# Esquematico.net
KiCad netlist of a schematic drawn in EAGLE
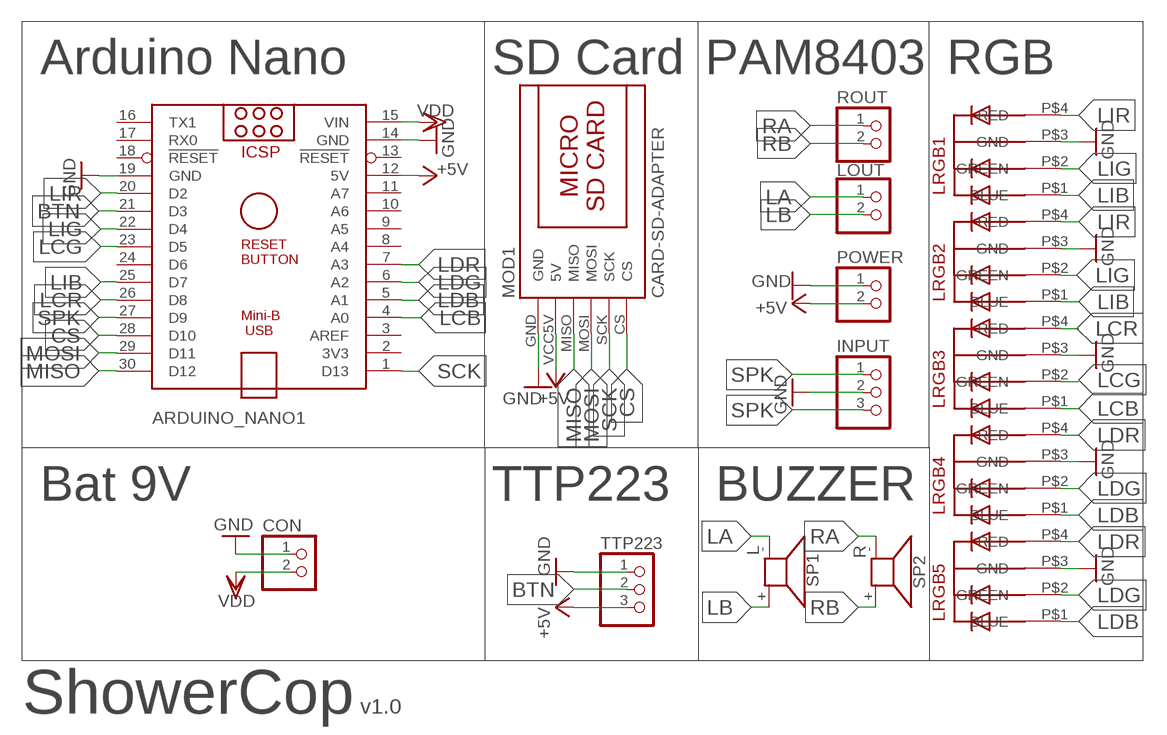
[diagram p0: schematic, sheet 1]

(export (version "E")
  (design (tool "Eeschema 10.0.6"))
  (components
    (comp (ref "ARDUINO_NANO1")
      (value "ARDUINO_NANO")
      (footprint "eagle-import:ARDUINO_NANO")
      (libsource (lib "eagle-import") (part "ARDUINO_NANO"))
    )
    (comp (ref "CON")
      (value "PINHD-1X2")
      (footprint "eagle-import:1X02")
      (libsource (lib "eagle-import") (part "PINHD-1X2"))
    )
    (comp (ref "INPUT")
      (value "PINHD-1X3")
      (footprint "eagle-import:1X03")
      (libsource (lib "eagle-import") (part "PINHD-1X3"))
    )
    (comp (ref "LOUT")
      (value "PINHD-1X2")
      (footprint "eagle-import:1X02")
      (libsource (lib "eagle-import") (part "PINHD-1X2"))
    )
    (comp (ref "LRGB1")
      (value "5MMRGBLED")
      (footprint "eagle-import:LED5MMRGB")
      (libsource (lib "eagle-import") (part "5MMRGBLED"))
    )
    (comp (ref "LRGB2")
      (value "5MMRGBLED")
      (footprint "eagle-import:LED5MMRGB")
      (libsource (lib "eagle-import") (part "5MMRGBLED"))
    )
    (comp (ref "LRGB3")
      (value "5MMRGBLED")
      (footprint "eagle-import:LED5MMRGB")
      (libsource (lib "eagle-import") (part "5MMRGBLED"))
    )
    (comp (ref "LRGB4")
      (value "5MMRGBLED")
      (footprint "eagle-import:LED5MMRGB")
      (libsource (lib "eagle-import") (part "5MMRGBLED"))
    )
    (comp (ref "LRGB5")
      (value "5MMRGBLED")
      (footprint "eagle-import:LED5MMRGB")
      (libsource (lib "eagle-import") (part "5MMRGBLED"))
    )
    (comp (ref "MOD1")
      (value "CARD-SD-ADAPTER")
      (footprint "eagle-import:CARD-SD-ADAPTER-CATALEX")
      (libsource (lib "eagle-import") (part "CARD-SD-ADAPTER-CATALEX"))
    )
    (comp (ref "POWER")
      (value "PINHD-1X2")
      (footprint "eagle-import:1X02")
      (libsource (lib "eagle-import") (part "PINHD-1X2"))
    )
    (comp (ref "ROUT")
      (value "PINHD-1X2")
      (footprint "eagle-import:1X02")
      (libsource (lib "eagle-import") (part "PINHD-1X2"))
    )
    (comp (ref "SP1")
      (value "L")
      (footprint "eagle-import:AL11P")
      (libsource (lib "eagle-import") (part "AL11P"))
    )
    (comp (ref "SP2")
      (value "R")
      (footprint "eagle-import:AL11P")
      (libsource (lib "eagle-import") (part "AL11P"))
    )
    (comp (ref "TTP223")
      (value "PINHD-1X3")
      (footprint "eagle-import:1X03")
      (libsource (lib "eagle-import") (part "PINHD-1X3"))
    )
  )
  (nets
    (net (code "1") (name "+5V") (class "Default")
      (node (ref "ARDUINO_NANO1") (pin "12") (pinfunction "5V_12") (pintype "power_in"))
      (node (ref "MOD1") (pin "VCC5V") (pinfunction "5V_VCC5V") (pintype "power_in"))
      (node (ref "POWER") (pin "2") (pinfunction "2_2") (pintype "passive"))
      (node (ref "TTP223") (pin "3") (pinfunction "3_3") (pintype "passive"))
    )
    (net (code "2") (name "BTN") (class "Default")
      (node (ref "ARDUINO_NANO1") (pin "21") (pinfunction "D3_21") (pintype "bidirectional"))
      (node (ref "TTP223") (pin "2") (pinfunction "2_2") (pintype "passive"))
    )
    (net (code "3") (name "CS") (class "Default")
      (node (ref "ARDUINO_NANO1") (pin "28") (pinfunction "D10_28") (pintype "bidirectional"))
      (node (ref "MOD1") (pin "CS") (pinfunction "CS_CS") (pintype "bidirectional"))
    )
    (net (code "4") (name "GND") (class "Default")
      (node (ref "ARDUINO_NANO1") (pin "14") (pinfunction "GND_14") (pintype "power_in"))
      (node (ref "ARDUINO_NANO1") (pin "19") (pinfunction "GND_19") (pintype "power_in"))
      (node (ref "CON") (pin "1") (pinfunction "1_1") (pintype "passive"))
      (node (ref "INPUT") (pin "2") (pinfunction "2_2") (pintype "passive"))
      (node (ref "LRGB1") (pin "P$3") (pinfunction "GND_P$3") (pintype "bidirectional"))
      (node (ref "LRGB2") (pin "P$3") (pinfunction "GND_P$3") (pintype "bidirectional"))
      (node (ref "LRGB3") (pin "P$3") (pinfunction "GND_P$3") (pintype "bidirectional"))
      (node (ref "LRGB4") (pin "P$3") (pinfunction "GND_P$3") (pintype "bidirectional"))
      (node (ref "LRGB5") (pin "P$3") (pinfunction "GND_P$3") (pintype "bidirectional"))
      (node (ref "MOD1") (pin "GND") (pinfunction "GND_GND") (pintype "power_in"))
      (node (ref "POWER") (pin "1") (pinfunction "1_1") (pintype "passive"))
      (node (ref "TTP223") (pin "1") (pinfunction "1_1") (pintype "passive"))
    )
    (net (code "5") (name "LA") (class "Default")
      (node (ref "LOUT") (pin "1") (pinfunction "1_1") (pintype "passive"))
      (node (ref "SP1") (pin "-") (pinfunction "1_-") (pintype "passive"))
    )
    (net (code "6") (name "LB") (class "Default")
      (node (ref "LOUT") (pin "2") (pinfunction "2_2") (pintype "passive"))
      (node (ref "SP1") (pin "+") (pinfunction "2_+") (pintype "passive"))
    )
    (net (code "7") (name "LCB") (class "Default")
      (node (ref "ARDUINO_NANO1") (pin "4") (pinfunction "A0_4") (pintype "bidirectional"))
      (node (ref "LRGB3") (pin "P$1") (pinfunction "BLUE_P$1") (pintype "bidirectional"))
    )
    (net (code "8") (name "LCG") (class "Default")
      (node (ref "ARDUINO_NANO1") (pin "23") (pinfunction "D5_23") (pintype "bidirectional"))
      (node (ref "LRGB3") (pin "P$2") (pinfunction "GREEN_P$2") (pintype "bidirectional"))
    )
    (net (code "9") (name "LCR") (class "Default")
      (node (ref "ARDUINO_NANO1") (pin "26") (pinfunction "D8_26") (pintype "bidirectional"))
      (node (ref "LRGB3") (pin "P$4") (pinfunction "RED_P$4") (pintype "bidirectional"))
    )
    (net (code "10") (name "LDB") (class "Default")
      (node (ref "ARDUINO_NANO1") (pin "5") (pinfunction "A1_5") (pintype "bidirectional"))
      (node (ref "LRGB4") (pin "P$1") (pinfunction "BLUE_P$1") (pintype "bidirectional"))
      (node (ref "LRGB5") (pin "P$1") (pinfunction "BLUE_P$1") (pintype "bidirectional"))
    )
    (net (code "11") (name "LDG") (class "Default")
      (node (ref "ARDUINO_NANO1") (pin "6") (pinfunction "A2_6") (pintype "bidirectional"))
      (node (ref "LRGB4") (pin "P$2") (pinfunction "GREEN_P$2") (pintype "bidirectional"))
      (node (ref "LRGB5") (pin "P$2") (pinfunction "GREEN_P$2") (pintype "bidirectional"))
    )
    (net (code "12") (name "LDR") (class "Default")
      (node (ref "ARDUINO_NANO1") (pin "7") (pinfunction "A3_7") (pintype "bidirectional"))
      (node (ref "LRGB4") (pin "P$4") (pinfunction "RED_P$4") (pintype "bidirectional"))
      (node (ref "LRGB5") (pin "P$4") (pinfunction "RED_P$4") (pintype "bidirectional"))
    )
    (net (code "13") (name "LIB") (class "Default")
      (node (ref "ARDUINO_NANO1") (pin "25") (pinfunction "D7_25") (pintype "bidirectional"))
      (node (ref "LRGB1") (pin "P$1") (pinfunction "BLUE_P$1") (pintype "bidirectional"))
      (node (ref "LRGB2") (pin "P$1") (pinfunction "BLUE_P$1") (pintype "bidirectional"))
    )
    (net (code "14") (name "LIG") (class "Default")
      (node (ref "ARDUINO_NANO1") (pin "22") (pinfunction "D4_22") (pintype "bidirectional"))
      (node (ref "LRGB1") (pin "P$2") (pinfunction "GREEN_P$2") (pintype "bidirectional"))
      (node (ref "LRGB2") (pin "P$2") (pinfunction "GREEN_P$2") (pintype "bidirectional"))
    )
    (net (code "15") (name "LIR") (class "Default")
      (node (ref "ARDUINO_NANO1") (pin "20") (pinfunction "D2_20") (pintype "bidirectional"))
      (node (ref "LRGB1") (pin "P$4") (pinfunction "RED_P$4") (pintype "bidirectional"))
      (node (ref "LRGB2") (pin "P$4") (pinfunction "RED_P$4") (pintype "bidirectional"))
    )
    (net (code "16") (name "MISO") (class "Default")
      (node (ref "ARDUINO_NANO1") (pin "30") (pinfunction "D12_30") (pintype "bidirectional"))
      (node (ref "MOD1") (pin "MISO") (pinfunction "MISO_MISO") (pintype "bidirectional"))
    )
    (net (code "17") (name "MOSI") (class "Default")
      (node (ref "ARDUINO_NANO1") (pin "29") (pinfunction "D11_29") (pintype "bidirectional"))
      (node (ref "MOD1") (pin "MOSI") (pinfunction "MOSI_MOSI") (pintype "bidirectional"))
    )
    (net (code "18") (name "RA") (class "Default")
      (node (ref "ROUT") (pin "1") (pinfunction "1_1") (pintype "passive"))
      (node (ref "SP2") (pin "-") (pinfunction "1_-") (pintype "passive"))
    )
    (net (code "19") (name "RB") (class "Default")
      (node (ref "ROUT") (pin "2") (pinfunction "2_2") (pintype "passive"))
      (node (ref "SP2") (pin "+") (pinfunction "2_+") (pintype "passive"))
    )
    (net (code "20") (name "SCK") (class "Default")
      (node (ref "ARDUINO_NANO1") (pin "1") (pinfunction "D13_1") (pintype "bidirectional"))
      (node (ref "MOD1") (pin "SCK") (pinfunction "SCK_SCK") (pintype "bidirectional"))
    )
    (net (code "21") (name "SPK") (class "Default")
      (node (ref "ARDUINO_NANO1") (pin "27") (pinfunction "D9_27") (pintype "bidirectional"))
      (node (ref "INPUT") (pin "1") (pinfunction "1_1") (pintype "passive"))
      (node (ref "INPUT") (pin "3") (pinfunction "3_3") (pintype "passive"))
    )
    (net (code "22") (name "VDD") (class "Default")
      (node (ref "ARDUINO_NANO1") (pin "15") (pinfunction "VIN_15") (pintype "power_in"))
      (node (ref "CON") (pin "2") (pinfunction "2_2") (pintype "passive"))
    )
    (net (code "23") (name "unconnected-(ARDUINO_NANO1-3V3-Pad2)") (class "Default")
      (node (ref "ARDUINO_NANO1") (pin "2") (pinfunction "3V3_2") (pintype "output"))
    )
    (net (code "24") (name "unconnected-(ARDUINO_NANO1-A4-Pad8)") (class "Default")
      (node (ref "ARDUINO_NANO1") (pin "8") (pinfunction "A4_8") (pintype "bidirectional"))
    )
    (net (code "25") (name "unconnected-(ARDUINO_NANO1-A5-Pad9)") (class "Default")
      (node (ref "ARDUINO_NANO1") (pin "9") (pinfunction "A5_9") (pintype "bidirectional"))
    )
    (net (code "26") (name "unconnected-(ARDUINO_NANO1-A6-Pad10)") (class "Default")
      (node (ref "ARDUINO_NANO1") (pin "10") (pinfunction "A6_10") (pintype "bidirectional"))
    )
    (net (code "27") (name "unconnected-(ARDUINO_NANO1-A7-Pad11)") (class "Default")
      (node (ref "ARDUINO_NANO1") (pin "11") (pinfunction "A7_11") (pintype "bidirectional"))
    )
    (net (code "28") (name "unconnected-(ARDUINO_NANO1-AREF-Pad3)") (class "Default")
      (node (ref "ARDUINO_NANO1") (pin "3") (pinfunction "AREF_3") (pintype "input"))
    )
    (net (code "29") (name "unconnected-(ARDUINO_NANO1-D6-Pad24)") (class "Default")
      (node (ref "ARDUINO_NANO1") (pin "24") (pinfunction "D6_24") (pintype "bidirectional"))
    )
    (net (code "30") (name "unconnected-(ARDUINO_NANO1-RX0-Pad17)") (class "Default")
      (node (ref "ARDUINO_NANO1") (pin "17") (pinfunction "RX0_17") (pintype "bidirectional"))
    )
    (net (code "31") (name "unconnected-(ARDUINO_NANO1-TX1-Pad16)") (class "Default")
      (node (ref "ARDUINO_NANO1") (pin "16") (pinfunction "TX1_16") (pintype "bidirectional"))
    )
    (net (code "32") (name "unconnected-(ARDUINO_NANO1-~{RESET}-Pad13)") (class "Default")
      (node (ref "ARDUINO_NANO1") (pin "13") (pinfunction "~{RESET}_13") (pintype "input"))
    )
    (net (code "33") (name "unconnected-(ARDUINO_NANO1-~{RESET}-Pad18)") (class "Default")
      (node (ref "ARDUINO_NANO1") (pin "18") (pinfunction "~{RESET}_18") (pintype "input"))
    )
  )
)
